# MainPCB.net
KiCad netlist of a schematic drawn in Altium Designer
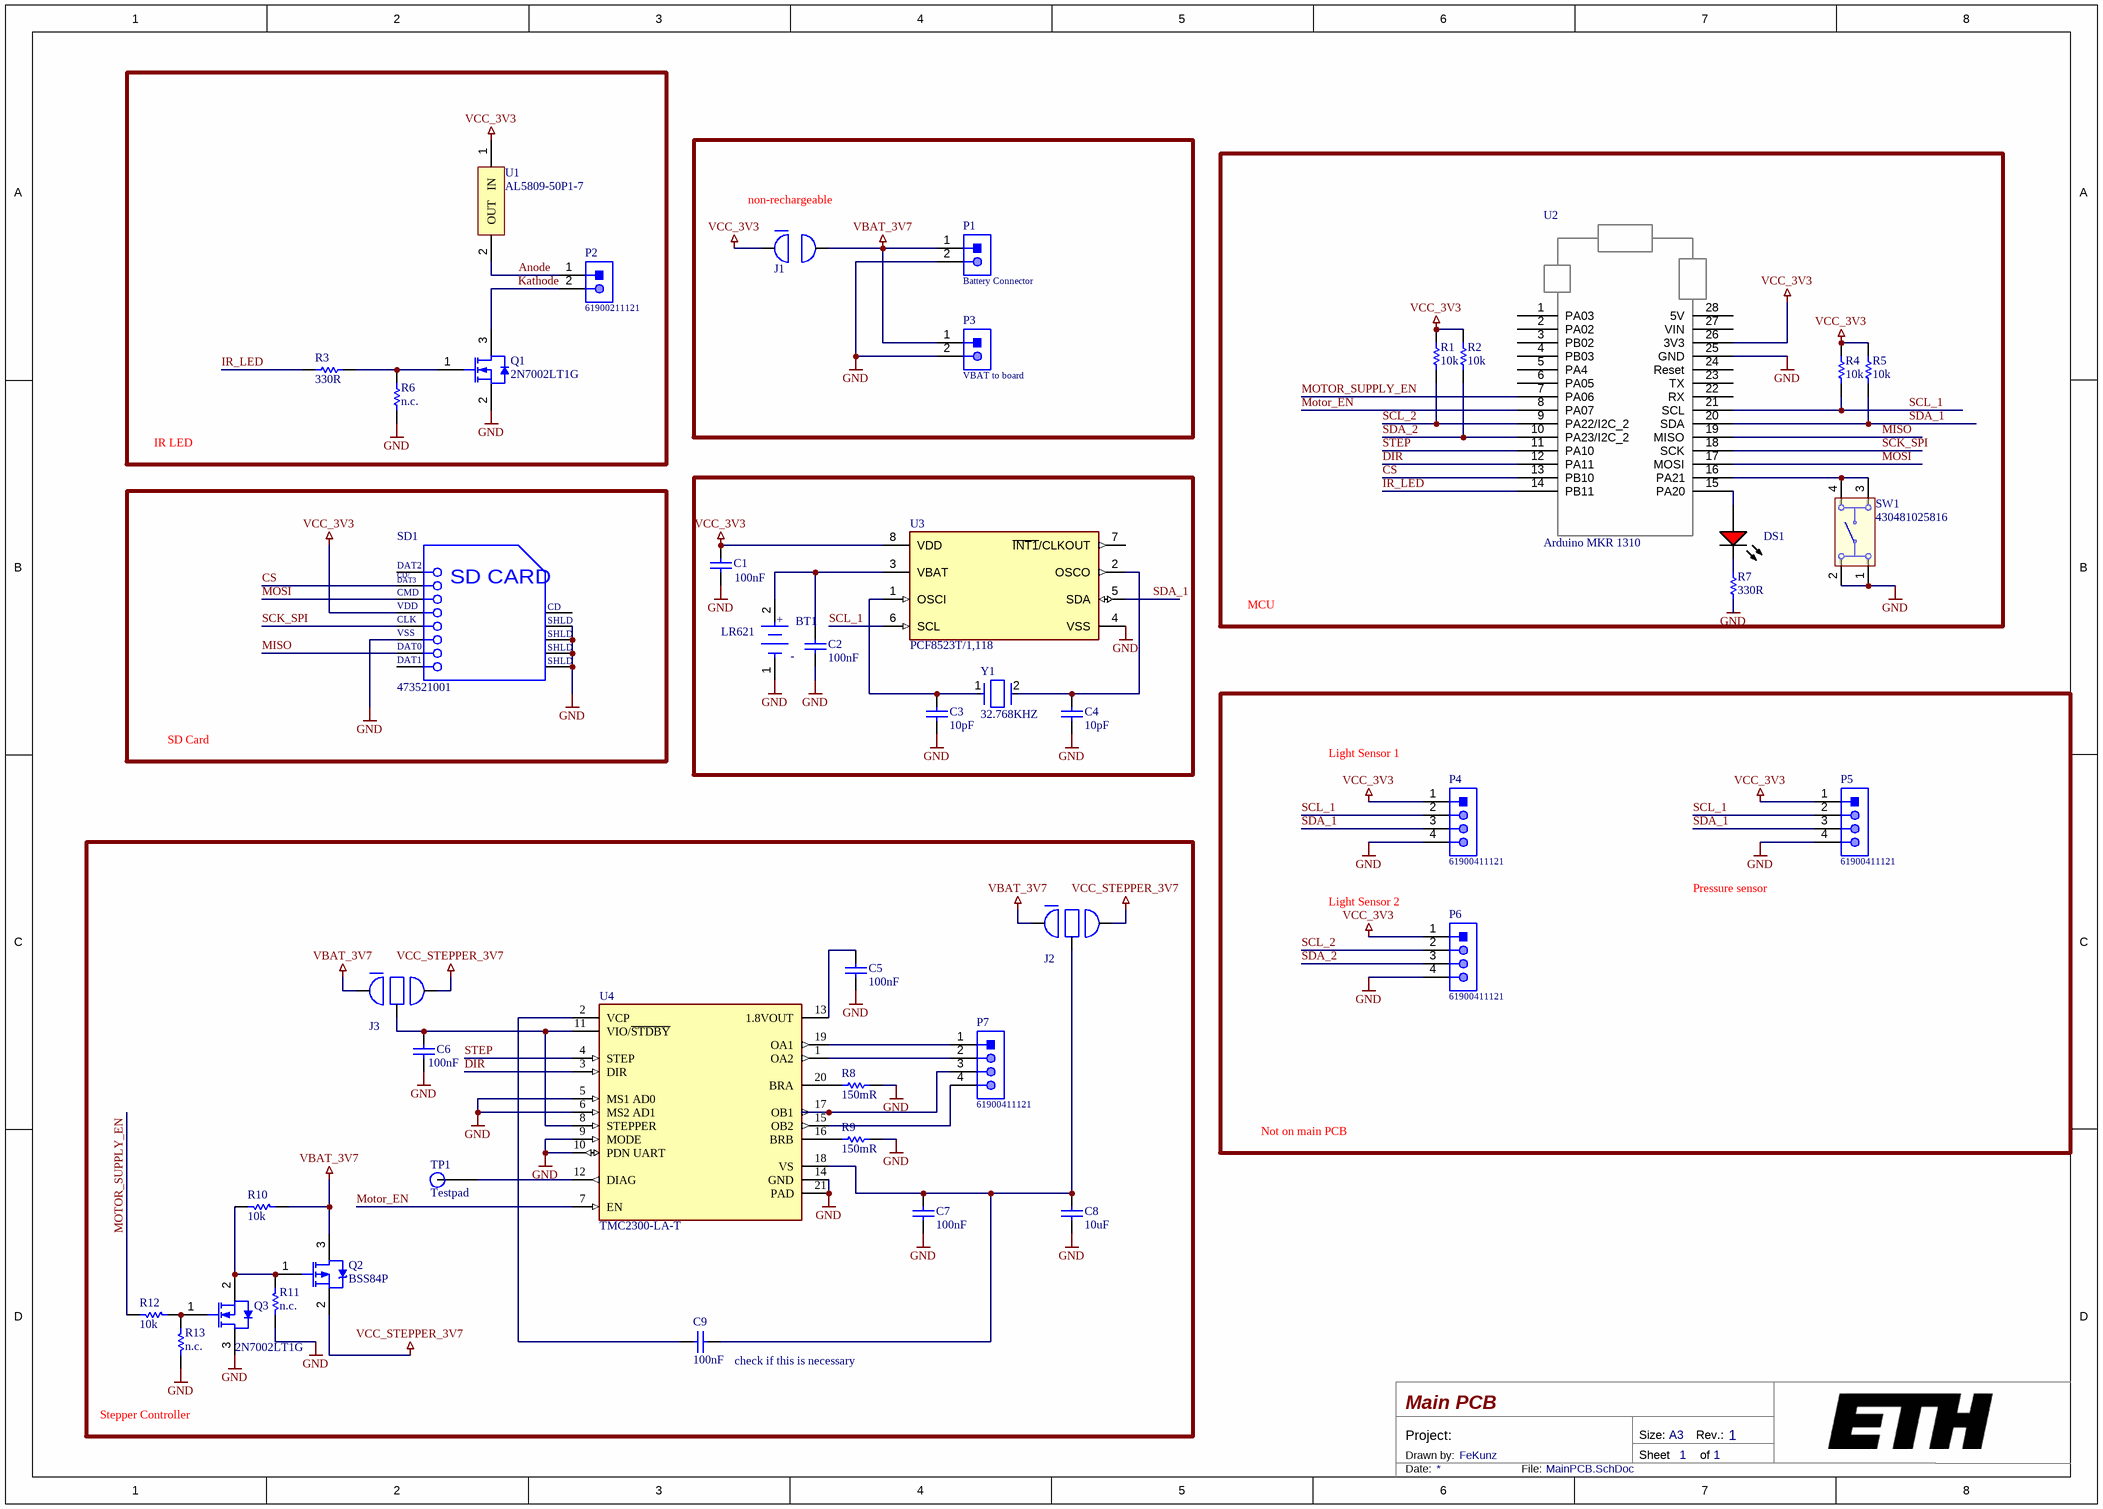
[diagram p0: MainPCB.SchDoc]

(export (version "E")
  (design (tool "Eeschema 10.0.6"))
  (components
    (comp (ref "BT1")
      (value "LR621")
      (footprint "FP-2998-MFG")
      (description "BATTERY RETAINER COIN 6.8MM SMD")
      (libsource (lib "Altium Content Vault") (part "60d3b5b901a8747834971d0eb8cf3fd"))
    )
    (comp (ref "C1")
      (value "100nF")
      (footprint "CAPC2013X140X50NL20T25")
      (fields
        (field (name "PART NUMBER") "08055C104K4Z2A")
        (field (name "MANUFACTURER") "AVX Interconnect / Elco")
      )
      (libsource (lib "Altium Content Vault") (part "CAP"))
    )
    (comp (ref "C2")
      (value "100nF")
      (footprint "CAPC2013X140X50NL20T25")
      (fields
        (field (name "PART NUMBER") "08055C104K4Z2A")
        (field (name "MANUFACTURER") "AVX Interconnect / Elco")
      )
      (libsource (lib "Altium Content Vault") (part "CAP"))
    )
    (comp (ref "C3")
      (value "10pF")
      (footprint "CAPC2013X115X51NL20T26")
      (fields
        (field (name "MANUFACTURER") "AVX Interconnect / Elco")
        (field (name "PART NUMBER") "08052U100GAT2A")
      )
      (libsource (lib "Altium Content Vault") (part "CAP"))
    )
    (comp (ref "C4")
      (value "10pF")
      (footprint "CAPC2013X115X51NL20T26")
      (fields
        (field (name "MANUFACTURER") "AVX Interconnect / Elco")
        (field (name "PART NUMBER") "08052U100GAT2A")
      )
      (libsource (lib "Altium Content Vault") (part "CAP"))
    )
    (comp (ref "C5")
      (value "100nF")
      (footprint "CAPC2013X140X50NL20T25")
      (fields
        (field (name "PART NUMBER") "08055C104K4Z2A")
        (field (name "MANUFACTURER") "AVX Interconnect / Elco")
      )
      (libsource (lib "Altium Content Vault") (part "CAP"))
    )
    (comp (ref "C6")
      (value "100nF")
      (footprint "CAPC2013X140X50NL20T25")
      (fields
        (field (name "PART NUMBER") "08055C104K4Z2A")
        (field (name "MANUFACTURER") "AVX Interconnect / Elco")
      )
      (libsource (lib "Altium Content Vault") (part "CAP"))
    )
    (comp (ref "C7")
      (value "100nF")
      (footprint "CAPC2013X140X50NL20T25")
      (fields
        (field (name "PART NUMBER") "08055C104K4Z2A")
        (field (name "MANUFACTURER") "AVX Interconnect / Elco")
      )
      (libsource (lib "Altium Content Vault") (part "CAP"))
    )
    (comp (ref "C8")
      (value "10uF")
      (footprint "CAPC2013X140X45NL15T25")
      (fields (field (name "PART NUMBER") "GRM21BR71A106KE51L") (field (name "MANUFACTURER") "Murata"))
      (libsource (lib "Altium Content Vault") (part "CAP"))
    )
    (comp (ref "C9")
      (value "100nF")
      (footprint "CAPC2013X140X50NL20T25")
      (fields
        (field (name "PART NUMBER") "08055C104K4Z2A")
        (field (name "MANUFACTURER") "AVX Interconnect / Elco")
      )
      (libsource (lib "Altium Content Vault") (part "CAP"))
    )
    (comp (ref "DS1")
      (value "HSMH-C190")
      (footprint "AVAG-HSMX-C190_V")
      (description "LED Uni-Color Red, 65 mW, 20 mA, -40 to 85 degC, 2-Pin SMD, RoHS, Tape and Reel")
      (libsource (lib "Altium Content Vault") (part "LED-RED-AK-2"))
    )
    (comp (ref "J1") (value "Jumper_2W") (footprint "2w_Jumper") (libsource (lib "SwS") (part "Jumper_2W")))
    (comp (ref "J2") (value "Jumper_3W") (footprint "3W_Jumper") (libsource (lib "SwS") (part "Jumper_3W")))
    (comp (ref "J3") (value "Jumper_3W") (footprint "3W_Jumper") (libsource (lib "SwS") (part "Jumper_3W")))
    (comp (ref "P1")
      (value "Battery Connector")
      (footprint "61900211121")
      (description "Male Locking Header WR-WTB, THT, Vertical, pitch 2.54 mm, 1 x 2 position")
      (fields
        (field (name "MANUFACTURER") "Wurth Elektronik")
        (field (name "PART NUMBER") "61900211121")
        (field (name "PUBLISHER") "WurthElektronik")
      )
      (libsource (lib "Altium Content Vault") (part "WE-CN-1P-M-R2"))
    )
    (comp (ref "P2")
      (value "61900211121")
      (footprint "61900211121")
      (description "Male Locking Header WR-WTB, THT, Vertical, pitch 2.54 mm, 1 x 2 position")
      (fields (field (name "MANUFACTURER") "Wurth Elektronik") (field (name "PUBLISHER") "WurthElektronik"))
      (libsource (lib "Altium Content Vault") (part "WE-CN-1P-M-R2"))
    )
    (comp (ref "P3")
      (value "VBAT to board")
      (footprint "61900211121")
      (description "Male Locking Header WR-WTB, THT, Vertical, pitch 2.54 mm, 1 x 2 position")
      (fields
        (field (name "MANUFACTURER") "Wurth Elektronik")
        (field (name "PART NUMBER") "61900211121")
        (field (name "PUBLISHER") "WurthElektronik")
      )
      (libsource (lib "Altium Content Vault") (part "WE-CN-1P-M-R2"))
    )
    (comp (ref "P4")
      (value "61900411121")
      (footprint "61900411121")
      (description "Male Locking Header WR-WTB, THT, Vertical, pitch 2.54 mm, 1 x 4 position")
      (fields (field (name "MANUFACTURER") "Wurth Elektronik") (field (name "PUBLISHER") "WurthElektronik"))
      (libsource (lib "Altium Content Vault") (part "WE-CN-1P-M-R4"))
    )
    (comp (ref "P5")
      (value "61900411121")
      (footprint "61900411121")
      (description "Male Locking Header WR-WTB, THT, Vertical, pitch 2.54 mm, 1 x 4 position")
      (fields (field (name "MANUFACTURER") "Wurth Elektronik") (field (name "PUBLISHER") "WurthElektronik"))
      (libsource (lib "Altium Content Vault") (part "WE-CN-1P-M-R4"))
    )
    (comp (ref "P6")
      (value "61900411121")
      (footprint "61900411121")
      (description "Male Locking Header WR-WTB, THT, Vertical, pitch 2.54 mm, 1 x 4 position")
      (fields (field (name "MANUFACTURER") "Wurth Elektronik") (field (name "PUBLISHER") "WurthElektronik"))
      (libsource (lib "Altium Content Vault") (part "WE-CN-1P-M-R4"))
    )
    (comp (ref "P7")
      (value "61900411121")
      (footprint "61900411121")
      (description "Male Locking Header WR-WTB, THT, Vertical, pitch 2.54 mm, 1 x 4 position")
      (fields (field (name "MANUFACTURER") "Wurth Elektronik") (field (name "PUBLISHER") "WurthElektronik"))
      (libsource (lib "Altium Content Vault") (part "WE-CN-1P-M-R4"))
    )
    (comp (ref "Q1")
      (value "2N7002LT1G")
      (footprint "ONSC-SOT-23-3-318-08_V")
      (description "Small Signal MOSFET, 60 V, 115 mA, N-Channel, 3-Pin SOT-23, Pb-Free, Tape and Reel")
      (fields (field (name "MANUFACTURER") "On Semiconductor"))
      (libsource (lib "Altium Content Vault") (part "ONSC-NMOS-G1S2D3-3"))
    )
    (comp (ref "Q2")
      (value "BSS84P")
      (footprint "INF-PG-SOT23_N")
      (fields (field (name "MANUFACTURER") "Infineon"))
      (libsource (lib "Altium Content Vault") (part "INF-PEMOS-GSD-3-B"))
    )
    (comp (ref "Q3")
      (value "2N7002LT1G")
      (footprint "ONSC-SOT-23-3-318-08_V")
      (description "Small Signal MOSFET, 60 V, 115 mA, N-Channel, 3-Pin SOT-23, Pb-Free, Tape and Reel")
      (fields (field (name "MANUFACTURER") "On Semiconductor"))
      (libsource (lib "Altium Content Vault") (part "ONSC-NMOS-G1S2D3-3"))
    )
    (comp (ref "R1")
      (value "10k")
      (footprint "RESC2013X60X35NL10T20")
      (description "Chip Resistor, 10 KOhm, +/- 1%, 0.125 W, -55 to 155 degC, 0805 (2012 Metric), RoHS, Tape and Reel")
      (fields (field (name "MANUFACTURER") "Yageo"))
      (libsource (lib "Altium Content Vault") (part "RES-2"))
    )
    (comp (ref "R2")
      (value "10k")
      (footprint "RESC2013X60X35NL10T20")
      (description "Chip Resistor, 10 KOhm, +/- 1%, 0.125 W, -55 to 155 degC, 0805 (2012 Metric), RoHS, Tape and Reel")
      (fields (field (name "MANUFACTURER") "Yageo"))
      (libsource (lib "Altium Content Vault") (part "RES-2"))
    )
    (comp (ref "R3")
      (value "330R")
      (footprint "RESC2013X60X40NL20T25")
      (fields (field (name "MANUFACTURER") "Panasonic") (field (name "PART NUMBER") "ERA6AEB221V"))
      (libsource (lib "Altium Content Vault") (part "RES"))
    )
    (comp (ref "R4")
      (value "10k")
      (footprint "RESC2013X60X35NL10T20")
      (description "Chip Resistor, 10 KOhm, +/- 1%, 0.125 W, -55 to 155 degC, 0805 (2012 Metric), RoHS, Tape and Reel")
      (fields (field (name "MANUFACTURER") "Yageo"))
      (libsource (lib "Altium Content Vault") (part "RES-2"))
    )
    (comp (ref "R5")
      (value "10k")
      (footprint "RESC2013X60X35NL10T20")
      (description "Chip Resistor, 10 KOhm, +/- 1%, 0.125 W, -55 to 155 degC, 0805 (2012 Metric), RoHS, Tape and Reel")
      (fields (field (name "MANUFACTURER") "Yageo"))
      (libsource (lib "Altium Content Vault") (part "RES-2"))
    )
    (comp (ref "R6")
      (value "n.c.")
      (footprint "RESC2013X60X35NL10T20")
      (description "Chip Resistor, 10 KOhm, +/- 1%, 0.125 W, -55 to 155 degC, 0805 (2012 Metric), RoHS, Tape and Reel")
      (fields (field (name "MANUFACTURER") "Yageo"))
      (libsource (lib "Altium Content Vault") (part "RES-2"))
    )
    (comp (ref "R7")
      (value "330R")
      (footprint "RESC2013X60X35LL10T20")
      (description "Chip Resistor, 330 Ohm, +/- 1%, 125 mW, -55 to 155 degC, 0805 (2012 Metric), RoHS, Tape and Reel")
      (fields (field (name "MANUFACTURER") "Yageo") (field (name "TOLERANCE") "1%"))
      (libsource (lib "Altium Content Vault") (part "RES-2"))
    )
    (comp (ref "R8")
      (value "150mR")
      (footprint "RESC2013X70X40LL20T20")
      (fields (field (name "MANUFACTURER") "Panasonic") (field (name "PART NUMBER") "ERJ6BSFR15V"))
      (libsource (lib "Altium Content Vault") (part "RES"))
    )
    (comp (ref "R9")
      (value "150mR")
      (footprint "RESC2013X70X40LL20T20")
      (fields (field (name "MANUFACTURER") "Panasonic") (field (name "PART NUMBER") "ERJ6BSFR15V"))
      (libsource (lib "Altium Content Vault") (part "RES"))
    )
    (comp (ref "R10")
      (value "10k")
      (footprint "RESC2013X60X40NL20T25")
      (fields (field (name "MANUFACTURER") "Panasonic") (field (name "PART NUMBER") "ERA6AEB221V"))
      (libsource (lib "Altium Content Vault") (part "RES"))
    )
    (comp (ref "R11")
      (value "n.c.")
      (footprint "RESC2013X60X35NL10T20")
      (description "Chip Resistor, 10 KOhm, +/- 1%, 0.125 W, -55 to 155 degC, 0805 (2012 Metric), RoHS, Tape and Reel")
      (fields (field (name "MANUFACTURER") "Yageo"))
      (libsource (lib "Altium Content Vault") (part "RES-2"))
    )
    (comp (ref "R12")
      (value "10k")
      (footprint "RESC2013X60X40NL20T25")
      (fields (field (name "MANUFACTURER") "Panasonic") (field (name "PART NUMBER") "ERA6AEB221V"))
      (libsource (lib "Altium Content Vault") (part "RES"))
    )
    (comp (ref "R13")
      (value "n.c.")
      (footprint "RESC2013X60X35NL10T20")
      (description "Chip Resistor, 10 KOhm, +/- 1%, 0.125 W, -55 to 155 degC, 0805 (2012 Metric), RoHS, Tape and Reel")
      (fields (field (name "MANUFACTURER") "Yageo"))
      (libsource (lib "Altium Content Vault") (part "RES-2"))
    )
    (comp (ref "SD1")
      (value "473521001")
      (footprint "MOLX-473521001_V")
      (description "MicroSD(TM), Pitch 1.1 mm, 8 Position, Height 1.88 mm, -20 to 85 degC, RoHS, Tape and Reel")
      (fields (field (name "MANUFACTURER") "Molex"))
      (libsource (lib "Altium Content Vault") (part "CN-SD-8-1SW-4S"))
    )
    (comp (ref "SW1")
      (value "430481025816")
      (footprint "430481025816")
      (description "WS-TASV SMD Tact Switch 6X6 mm")
      (fields (field (name "MANUFACTURER") "Wuerth Elektronik"))
      (libsource (lib "Altium Content Vault") (part "WE-TACT-SW-4_A"))
    )
    (comp (ref "TP1") (value "Testpad") (footprint "Testpad") (libsource (lib "SwS") (part "Testpad")))
    (comp (ref "U1")
      (value "AL5809-50P1-7")
      (footprint "DIOD-POWERDI123-2_B_V")
      (description "Constant Current LED Driver, 2.5 to 60 V, -40 to 125 degC, 2-Pin SMD, RoHS, Tape and Reel")
      (libsource (lib "Altium Content Vault") (part "DIOD-AL5809-2"))
    )
    (comp (ref "U2")
      (value "Arduino MKR 1310")
      (footprint "ArduinoMKR")
      (libsource (lib "SwS") (part "Arduino MKR"))
    )
    (comp (ref "U3")
      (value "PCF8523T/1,118")
      (footprint "FP-SOT96-1-IPC_C")
      (description "IC RTC CLK/CALENDAR I2C 8-SOIC")
      (libsource (lib "Altium Content Vault") (part "848ef7d52730a566ae52f9242454426"))
    )
    (comp (ref "U4")
      (value "TMC2300-LA-T")
      (footprint "FP-TMC2300-LA-T-IPC_C")
      (description "LOW VOLTAGE MOTOR DRIVER 2-11V Q")
      (libsource (lib "Altium Content Vault") (part "1441b42700c3d6e1cb320d294525ede"))
    )
    (comp (ref "Y1")
      (value "32.768KHZ")
      (footprint "FP-ABS05-MFG")
      (description "CRYSTAL 32.7680KHZ 12.5PF SMD")
      (fields (field (name "TOLERANCE") "20ppm"))
      (libsource (lib "Altium Content Vault") (part "c23a69dc6c9e2f18f2079038eb95dd1"))
    )
  )
  (nets
    (net (code "1") (name "/Anode") (class "Default")
      (node (ref "P2") (pin "1") (pinfunction "1_1") (pintype "passive"))
      (node (ref "U1") (pin "2") (pinfunction "OUT_2") (pintype "passive"))
    )
    (net (code "2") (name "/CS") (class "Default")
      (node (ref "SD1") (pin "2") (pinfunction "CD/DAT3_2") (pintype "passive"))
      (node (ref "U2") (pin "13") (pinfunction "PB10_13") (pintype "passive"))
    )
    (net (code "3") (name "/DIR") (class "Default")
      (node (ref "U2") (pin "12") (pinfunction "PA11_12") (pintype "passive"))
      (node (ref "U4") (pin "3") (pinfunction "DIR_3") (pintype "input"))
    )
    (net (code "4") (name "/IR_LED") (class "Default")
      (node (ref "R3") (pin "1") (pinfunction "1_1") (pintype "passive"))
      (node (ref "U2") (pin "14") (pinfunction "PB11_14") (pintype "passive"))
    )
    (net (code "5") (name "/Kathode") (class "Default")
      (node (ref "P2") (pin "2") (pinfunction "2_2") (pintype "passive"))
      (node (ref "Q1") (pin "3") (pinfunction "D_3") (pintype "passive"))
    )
    (net (code "6") (name "/MISO") (class "Default")
      (node (ref "SD1") (pin "7") (pinfunction "DAT0_7") (pintype "passive"))
      (node (ref "U2") (pin "19") (pinfunction "MISO_19") (pintype "passive"))
    )
    (net (code "7") (name "/MOSI") (class "Default")
      (node (ref "SD1") (pin "3") (pinfunction "CMD_3") (pintype "passive"))
      (node (ref "U2") (pin "17") (pinfunction "MOSI_17") (pintype "passive"))
    )
    (net (code "8") (name "/MOTOR_SUPPLY_EN") (class "Default")
      (node (ref "R12") (pin "1") (pinfunction "1_1") (pintype "passive"))
      (node (ref "U2") (pin "7") (pinfunction "PA06_7") (pintype "passive"))
    )
    (net (code "9") (name "/Motor_EN") (class "Default")
      (node (ref "U2") (pin "8") (pinfunction "PA07_8") (pintype "passive"))
      (node (ref "U4") (pin "7") (pinfunction "EN_7") (pintype "input"))
    )
    (net (code "10") (name "/SCK_SPI") (class "Default")
      (node (ref "SD1") (pin "5") (pinfunction "CLK_5") (pintype "passive"))
      (node (ref "U2") (pin "18") (pinfunction "SCK_18") (pintype "passive"))
    )
    (net (code "11") (name "/SCL_1") (class "Default")
      (node (ref "P4") (pin "2") (pinfunction "2_2") (pintype "passive"))
      (node (ref "P5") (pin "2") (pinfunction "2_2") (pintype "passive"))
      (node (ref "R4") (pin "1") (pinfunction "1_1") (pintype "passive"))
      (node (ref "U2") (pin "21") (pinfunction "SCL_21") (pintype "passive"))
      (node (ref "U3") (pin "6") (pinfunction "SCL_6") (pintype "input"))
    )
    (net (code "12") (name "/SCL_2") (class "Default")
      (node (ref "P6") (pin "2") (pinfunction "2_2") (pintype "passive"))
      (node (ref "R1") (pin "1") (pinfunction "1_1") (pintype "passive"))
      (node (ref "U2") (pin "9") (pinfunction "PA22/I2C_2_9") (pintype "passive"))
    )
    (net (code "13") (name "/SDA_1") (class "Default")
      (node (ref "P4") (pin "3") (pinfunction "3_3") (pintype "passive"))
      (node (ref "P5") (pin "3") (pinfunction "3_3") (pintype "passive"))
      (node (ref "R5") (pin "1") (pinfunction "1_1") (pintype "passive"))
      (node (ref "U2") (pin "20") (pinfunction "SDA_20") (pintype "passive"))
      (node (ref "U3") (pin "5") (pinfunction "SDA_5") (pintype "bidirectional"))
    )
    (net (code "14") (name "/SDA_2") (class "Default")
      (node (ref "P6") (pin "3") (pinfunction "3_3") (pintype "passive"))
      (node (ref "R2") (pin "1") (pinfunction "1_1") (pintype "passive"))
      (node (ref "U2") (pin "10") (pinfunction "PA23/I2C_2_10") (pintype "passive"))
    )
    (net (code "15") (name "/STEP") (class "Default")
      (node (ref "U2") (pin "11") (pinfunction "PA10_11") (pintype "passive"))
      (node (ref "U4") (pin "4") (pinfunction "STEP_4") (pintype "input"))
    )
    (net (code "16") (name "GND") (class "Default")
      (node (ref "BT1") (pin "1") (pinfunction "C_1") (pintype "passive"))
      (node (ref "C1") (pin "1") (pinfunction "1_1") (pintype "passive"))
      (node (ref "C2") (pin "1") (pinfunction "1_1") (pintype "passive"))
      (node (ref "C3") (pin "1") (pinfunction "1_1") (pintype "passive"))
      (node (ref "C4") (pin "1") (pinfunction "1_1") (pintype "passive"))
      (node (ref "C5") (pin "1") (pinfunction "1_1") (pintype "passive"))
      (node (ref "C6") (pin "1") (pinfunction "1_1") (pintype "passive"))
      (node (ref "C7") (pin "2") (pinfunction "2_2") (pintype "passive"))
      (node (ref "C8") (pin "1") (pinfunction "1_1") (pintype "passive"))
      (node (ref "P1") (pin "2") (pinfunction "2_2") (pintype "passive"))
      (node (ref "P3") (pin "2") (pinfunction "2_2") (pintype "passive"))
      (node (ref "P4") (pin "4") (pinfunction "4_4") (pintype "passive"))
      (node (ref "P5") (pin "4") (pinfunction "4_4") (pintype "passive"))
      (node (ref "P6") (pin "4") (pinfunction "4_4") (pintype "passive"))
      (node (ref "Q1") (pin "2") (pinfunction "S_2") (pintype "passive"))
      (node (ref "Q3") (pin "3") (pinfunction "D_3") (pintype "passive"))
      (node (ref "R11") (pin "2") (pinfunction "2_2") (pintype "passive"))
      (node (ref "R13") (pin "2") (pinfunction "2_2") (pintype "passive"))
      (node (ref "R6") (pin "1") (pinfunction "1_1") (pintype "passive"))
      (node (ref "R7") (pin "2") (pinfunction "2_2") (pintype "passive"))
      (node (ref "R8") (pin "2") (pinfunction "2_2") (pintype "passive"))
      (node (ref "R9") (pin "2") (pinfunction "2_2") (pintype "passive"))
      (node (ref "SD1") (pin "10") (pinfunction "SHLD_10") (pintype "passive"))
      (node (ref "SD1") (pin "11") (pinfunction "SHLD_11") (pintype "passive"))
      (node (ref "SD1") (pin "12") (pinfunction "SHLD_12") (pintype "passive"))
      (node (ref "SD1") (pin "13") (pinfunction "SHLD_13") (pintype "passive"))
      (node (ref "SD1") (pin "6") (pinfunction "VSS_6") (pintype "passive"))
      (node (ref "SW1") (pin "1") (pinfunction "1_1") (pintype "passive"))
      (node (ref "SW1") (pin "2") (pinfunction "2_2") (pintype "passive"))
      (node (ref "U2") (pin "25") (pinfunction "GND_25") (pintype "passive"))
      (node (ref "U3") (pin "4") (pinfunction "VSS_4") (pintype "power_in"))
      (node (ref "U4") (pin "10") (pinfunction "PDN_UART_10") (pintype "bidirectional"))
      (node (ref "U4") (pin "14") (pinfunction "GND_14") (pintype "power_in"))
      (node (ref "U4") (pin "21") (pinfunction "PAD_21") (pintype "passive"))
      (node (ref "U4") (pin "5") (pinfunction "MS1_AD0_5") (pintype "input"))
      (node (ref "U4") (pin "6") (pinfunction "MS2_AD1_6") (pintype "input"))
      (node (ref "U4") (pin "9") (pinfunction "MODE_9") (pintype "input"))
    )
    (net (code "17") (name "Net-(BT1-A)") (class "Default")
      (node (ref "BT1") (pin "2") (pinfunction "A_2") (pintype "passive"))
      (node (ref "C2") (pin "2") (pinfunction "2_2") (pintype "passive"))
      (node (ref "U3") (pin "3") (pinfunction "VBAT_3") (pintype "power_in"))
    )
    (net (code "18") (name "Net-(DS1-A)") (class "Default")
      (node (ref "DS1") (pin "1") (pinfunction "A_1") (pintype "passive"))
      (node (ref "U2") (pin "15") (pinfunction "PA20_15") (pintype "passive"))
    )
    (net (code "19") (name "Net-(DS1-K)") (class "Default")
      (node (ref "DS1") (pin "2") (pinfunction "K_2") (pintype "passive"))
      (node (ref "R7") (pin "1") (pinfunction "1_1") (pintype "passive"))
    )
    (net (code "20") (name "Net-(J2-4)") (class "Default")
      (node (ref "C7") (pin "1") (pinfunction "1_1") (pintype "passive"))
      (node (ref "C8") (pin "2") (pinfunction "2_2") (pintype "passive"))
      (node (ref "C9") (pin "1") (pinfunction "1_1") (pintype "passive"))
      (node (ref "J2") (pin "2") (pinfunction "4_2") (pintype "passive"))
      (node (ref "U4") (pin "18") (pinfunction "VS_18") (pintype "power_in"))
    )
    (net (code "21") (name "Net-(J3-4)") (class "Default")
      (node (ref "C6") (pin "2") (pinfunction "2_2") (pintype "passive"))
      (node (ref "J3") (pin "2") (pinfunction "4_2") (pintype "passive"))
      (node (ref "U4") (pin "11") (pinfunction "VIO/~{STDBY}_11") (pintype "passive"))
      (node (ref "U4") (pin "8") (pinfunction "STEPPER_8") (pintype "input"))
    )
    (net (code "22") (name "Net-(Q1-G)") (class "Default")
      (node (ref "Q1") (pin "1") (pinfunction "G_1") (pintype "passive"))
      (node (ref "R3") (pin "2") (pinfunction "2_2") (pintype "passive"))
      (node (ref "R6") (pin "2") (pinfunction "2_2") (pintype "passive"))
    )
    (net (code "23") (name "Net-(Q2-GATE)") (class "Default")
      (node (ref "Q2") (pin "1") (pinfunction "GATE_1") (pintype "passive"))
      (node (ref "Q3") (pin "2") (pinfunction "S_2") (pintype "passive"))
      (node (ref "R10") (pin "1") (pinfunction "1_1") (pintype "passive"))
      (node (ref "R11") (pin "1") (pinfunction "1_1") (pintype "passive"))
    )
    (net (code "24") (name "Net-(Q3-G)") (class "Default")
      (node (ref "Q3") (pin "1") (pinfunction "G_1") (pintype "passive"))
      (node (ref "R12") (pin "2") (pinfunction "2_2") (pintype "passive"))
      (node (ref "R13") (pin "1") (pinfunction "1_1") (pintype "passive"))
    )
    (net (code "25") (name "Net-(U2-PA21)") (class "Default")
      (node (ref "SW1") (pin "3") (pinfunction "3_3") (pintype "passive"))
      (node (ref "SW1") (pin "4") (pinfunction "4_4") (pintype "passive"))
      (node (ref "U2") (pin "16") (pinfunction "PA21_16") (pintype "passive"))
    )
    (net (code "26") (name "Net-(U3-OSCI)") (class "Default")
      (node (ref "C3") (pin "2") (pinfunction "2_2") (pintype "passive"))
      (node (ref "U3") (pin "1") (pinfunction "OSCI_1") (pintype "input"))
      (node (ref "Y1") (pin "1") (pinfunction "1_1") (pintype "passive"))
    )
    (net (code "27") (name "Net-(U3-OSCO)") (class "Default")
      (node (ref "C4") (pin "2") (pinfunction "2_2") (pintype "passive"))
      (node (ref "U3") (pin "2") (pinfunction "OSCO_2") (pintype "output"))
      (node (ref "Y1") (pin "2") (pinfunction "2_2") (pintype "passive"))
    )
    (net (code "28") (name "Net-(U4-1.8VOUT)") (class "Default")
      (node (ref "C5") (pin "2") (pinfunction "2_2") (pintype "passive"))
      (node (ref "U4") (pin "13") (pinfunction "1.8VOUT_13") (pintype "power_in"))
    )
    (net (code "29") (name "Net-(U4-BRA)") (class "Default")
      (node (ref "R8") (pin "1") (pinfunction "1_1") (pintype "passive"))
      (node (ref "U4") (pin "20") (pinfunction "BRA_20") (pintype "passive"))
    )
    (net (code "30") (name "Net-(U4-BRB)") (class "Default")
      (node (ref "R9") (pin "1") (pinfunction "1_1") (pintype "passive"))
      (node (ref "U4") (pin "16") (pinfunction "BRB_16") (pintype "passive"))
    )
    (net (code "31") (name "Net-(U4-DIAG)") (class "Default")
      (node (ref "TP1") (pin "1") (pinfunction "1_1") (pintype "passive"))
      (node (ref "U4") (pin "12") (pinfunction "DIAG_12") (pintype "output"))
    )
    (net (code "32") (name "Net-(U4-OA1)") (class "Default")
      (node (ref "P7") (pin "1") (pinfunction "1_1") (pintype "passive"))
      (node (ref "U4") (pin "19") (pinfunction "OA1_19") (pintype "output"))
    )
    (net (code "33") (name "Net-(U4-OA2)") (class "Default")
      (node (ref "P7") (pin "2") (pinfunction "2_2") (pintype "passive"))
      (node (ref "U4") (pin "1") (pinfunction "OA2_1") (pintype "output"))
    )
    (net (code "34") (name "Net-(U4-OB1)") (class "Default")
      (node (ref "P7") (pin "3") (pinfunction "3_3") (pintype "passive"))
      (node (ref "U4") (pin "17") (pinfunction "OB1_17") (pintype "output"))
    )
    (net (code "35") (name "Net-(U4-OB2)") (class "Default")
      (node (ref "P7") (pin "4") (pinfunction "4_4") (pintype "passive"))
      (node (ref "U4") (pin "15") (pinfunction "OB2_15") (pintype "output"))
    )
    (net (code "36") (name "Net-(U4-VCP)") (class "Default")
      (node (ref "C9") (pin "2") (pinfunction "2_2") (pintype "passive"))
      (node (ref "U4") (pin "2") (pinfunction "VCP_2") (pintype "power_in"))
    )
    (net (code "37") (name "VBAT_3V7") (class "Default")
      (node (ref "J1") (pin "2") (pinfunction "3_2") (pintype "passive"))
      (node (ref "J2") (pin "1") (pinfunction "2_1") (pintype "passive"))
      (node (ref "J3") (pin "1") (pinfunction "2_1") (pintype "passive"))
      (node (ref "P1") (pin "1") (pinfunction "1_1") (pintype "passive"))
      (node (ref "P3") (pin "1") (pinfunction "1_1") (pintype "passive"))
      (node (ref "Q2") (pin "3") (pinfunction "DRAIN_3") (pintype "passive"))
      (node (ref "R10") (pin "2") (pinfunction "2_2") (pintype "passive"))
    )
    (net (code "38") (name "VCC_3V3") (class "Default")
      (node (ref "C1") (pin "2") (pinfunction "2_2") (pintype "passive"))
      (node (ref "J1") (pin "1") (pinfunction "2_1") (pintype "passive"))
      (node (ref "P4") (pin "1") (pinfunction "1_1") (pintype "passive"))
      (node (ref "P5") (pin "1") (pinfunction "1_1") (pintype "passive"))
      (node (ref "P6") (pin "1") (pinfunction "1_1") (pintype "passive"))
      (node (ref "R1") (pin "2") (pinfunction "2_2") (pintype "passive"))
      (node (ref "R2") (pin "2") (pinfunction "2_2") (pintype "passive"))
      (node (ref "R4") (pin "2") (pinfunction "2_2") (pintype "passive"))
      (node (ref "R5") (pin "2") (pinfunction "2_2") (pintype "passive"))
      (node (ref "SD1") (pin "4") (pinfunction "VDD_4") (pintype "passive"))
      (node (ref "U1") (pin "1") (pinfunction "IN_1") (pintype "passive"))
      (node (ref "U2") (pin "26") (pinfunction "3V3_26") (pintype "passive"))
      (node (ref "U3") (pin "8") (pinfunction "VDD_8") (pintype "power_in"))
    )
    (net (code "39") (name "VCC_STEPPER_3V7") (class "Default")
      (node (ref "J2") (pin "3") (pinfunction "3_3") (pintype "passive"))
      (node (ref "J3") (pin "3") (pinfunction "3_3") (pintype "passive"))
      (node (ref "Q2") (pin "2") (pinfunction "SOURCE_2") (pintype "passive"))
    )
    (net (code "40") (name "unconnected-(SD1-CD-Pad9)") (class "Default")
      (node (ref "SD1") (pin "9") (pinfunction "CD_9") (pintype "passive"))
    )
    (net (code "41") (name "unconnected-(SD1-DAT1-Pad8)") (class "Default")
      (node (ref "SD1") (pin "8") (pinfunction "DAT1_8") (pintype "passive"))
    )
    (net (code "42") (name "unconnected-(SD1-DAT2-Pad1)") (class "Default")
      (node (ref "SD1") (pin "1") (pinfunction "DAT2_1") (pintype "passive"))
    )
    (net (code "43") (name "unconnected-(U2-5V-Pad28)") (class "Default")
      (node (ref "U2") (pin "28") (pinfunction "5V_28") (pintype "passive"))
    )
    (net (code "44") (name "unconnected-(U2-PA02-Pad2)") (class "Default")
      (node (ref "U2") (pin "2") (pinfunction "PA02_2") (pintype "passive"))
    )
    (net (code "45") (name "unconnected-(U2-PA03-Pad1)") (class "Default")
      (node (ref "U2") (pin "1") (pinfunction "PA03_1") (pintype "passive"))
    )
    (net (code "46") (name "unconnected-(U2-PA4-Pad5)") (class "Default")
      (node (ref "U2") (pin "5") (pinfunction "PA4_5") (pintype "passive"))
    )
    (net (code "47") (name "unconnected-(U2-PA05-Pad6)") (class "Default")
      (node (ref "U2") (pin "6") (pinfunction "PA05_6") (pintype "passive"))
    )
    (net (code "48") (name "unconnected-(U2-PB02-Pad3)") (class "Default")
      (node (ref "U2") (pin "3") (pinfunction "PB02_3") (pintype "passive"))
    )
    (net (code "49") (name "unconnected-(U2-PB03-Pad4)") (class "Default")
      (node (ref "U2") (pin "4") (pinfunction "PB03_4") (pintype "passive"))
    )
    (net (code "50") (name "unconnected-(U2-RX-Pad22)") (class "Default")
      (node (ref "U2") (pin "22") (pinfunction "RX_22") (pintype "passive"))
    )
    (net (code "51") (name "unconnected-(U2-Reset-Pad24)") (class "Default")
      (node (ref "U2") (pin "24") (pinfunction "Reset_24") (pintype "passive"))
    )
    (net (code "52") (name "unconnected-(U2-TX-Pad23)") (class "Default")
      (node (ref "U2") (pin "23") (pinfunction "TX_23") (pintype "passive"))
    )
    (net (code "53") (name "unconnected-(U2-VIN-Pad27)") (class "Default")
      (node (ref "U2") (pin "27") (pinfunction "VIN_27") (pintype "passive"))
    )
    (net (code "54") (name "unconnected-(U3-~{INT1}{slash}CLKOUT-Pad7)") (class "Default")
      (node (ref "U3") (pin "7") (pinfunction "~{INT1}/CLKOUT_7") (pintype "output"))
    )
  )
)
